# connector_flow.net
KiCad netlist of a schematic drawn in Altium Designer
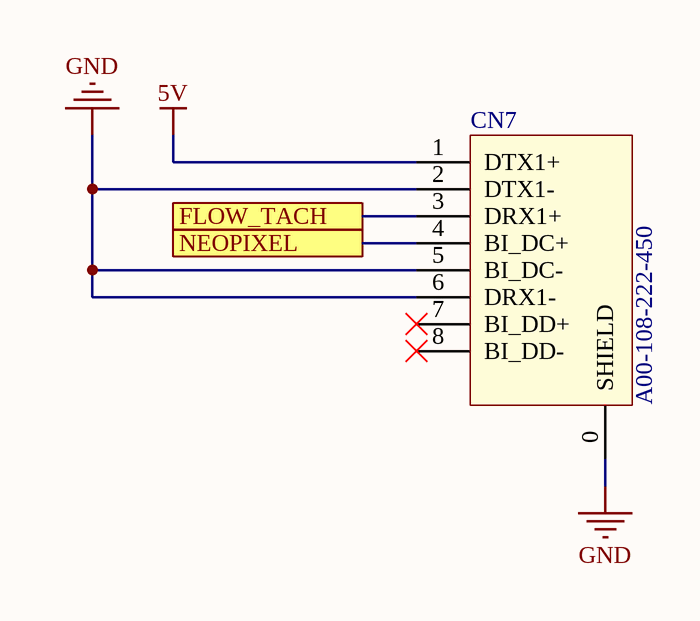
[diagram p0: connector_flow.SchDoc]

(export (version "E")
  (design (tool "Eeschema 10.0.6"))
  (components
    (comp (ref "CN7")
      (value "CONN_RJ45_TOP_A00-108-222-450")
      (footprint "RJ45 TOP ENTRY EDAC A00-108-222-450")
      (description "CONN, RJ-45, 1-PORT, 8-POS, VERT, 0.76um GOLD, TH")
      (fields (field (name "MFG") "EDAC Inc") (field (name "MFG P/N") "A00-108-222-450"))
      (libsource (lib "AltiumReleaseLibDB") (part "CONN_RJ45_TOP_A00-108-222-450"))
    )
  )
  (nets
    (net (code "1") (name "/FLOW_TACH") (class "Default")
      (node (ref "CN7") (pin "3") (pinfunction "DRX1+_3") (pintype "passive"))
    )
    (net (code "2") (name "/NEOPIXEL") (class "Default")
      (node (ref "CN7") (pin "4") (pinfunction "BI_DC+_4") (pintype "passive"))
    )
    (net (code "3") (name "5V") (class "Default")
      (node (ref "CN7") (pin "1") (pinfunction "DTX1+_1") (pintype "passive"))
    )
    (net (code "4") (name "GND") (class "Default")
      (node (ref "CN7") (pin "0") (pinfunction "SHIELD_0") (pintype "passive"))
      (node (ref "CN7") (pin "2") (pinfunction "DTX1-_2") (pintype "passive"))
      (node (ref "CN7") (pin "5") (pinfunction "BI_DC-_5") (pintype "passive"))
      (node (ref "CN7") (pin "6") (pinfunction "DRX1-_6") (pintype "passive"))
    )
    (net (code "5") (name "unconnected-(CN7-BI_DD+-Pad7)") (class "Default")
      (node (ref "CN7") (pin "7") (pinfunction "BI_DD+_7") (pintype "passive+no_connect"))
    )
    (net (code "6") (name "unconnected-(CN7-BI_DD--Pad8)") (class "Default")
      (node (ref "CN7") (pin "8") (pinfunction "BI_DD-_8") (pintype "passive+no_connect"))
    )
  )
)
